# CrowPanel_ESP32_Display-4_3-inch-V2_1-20.net
KiCad netlist of a schematic drawn in EAGLE
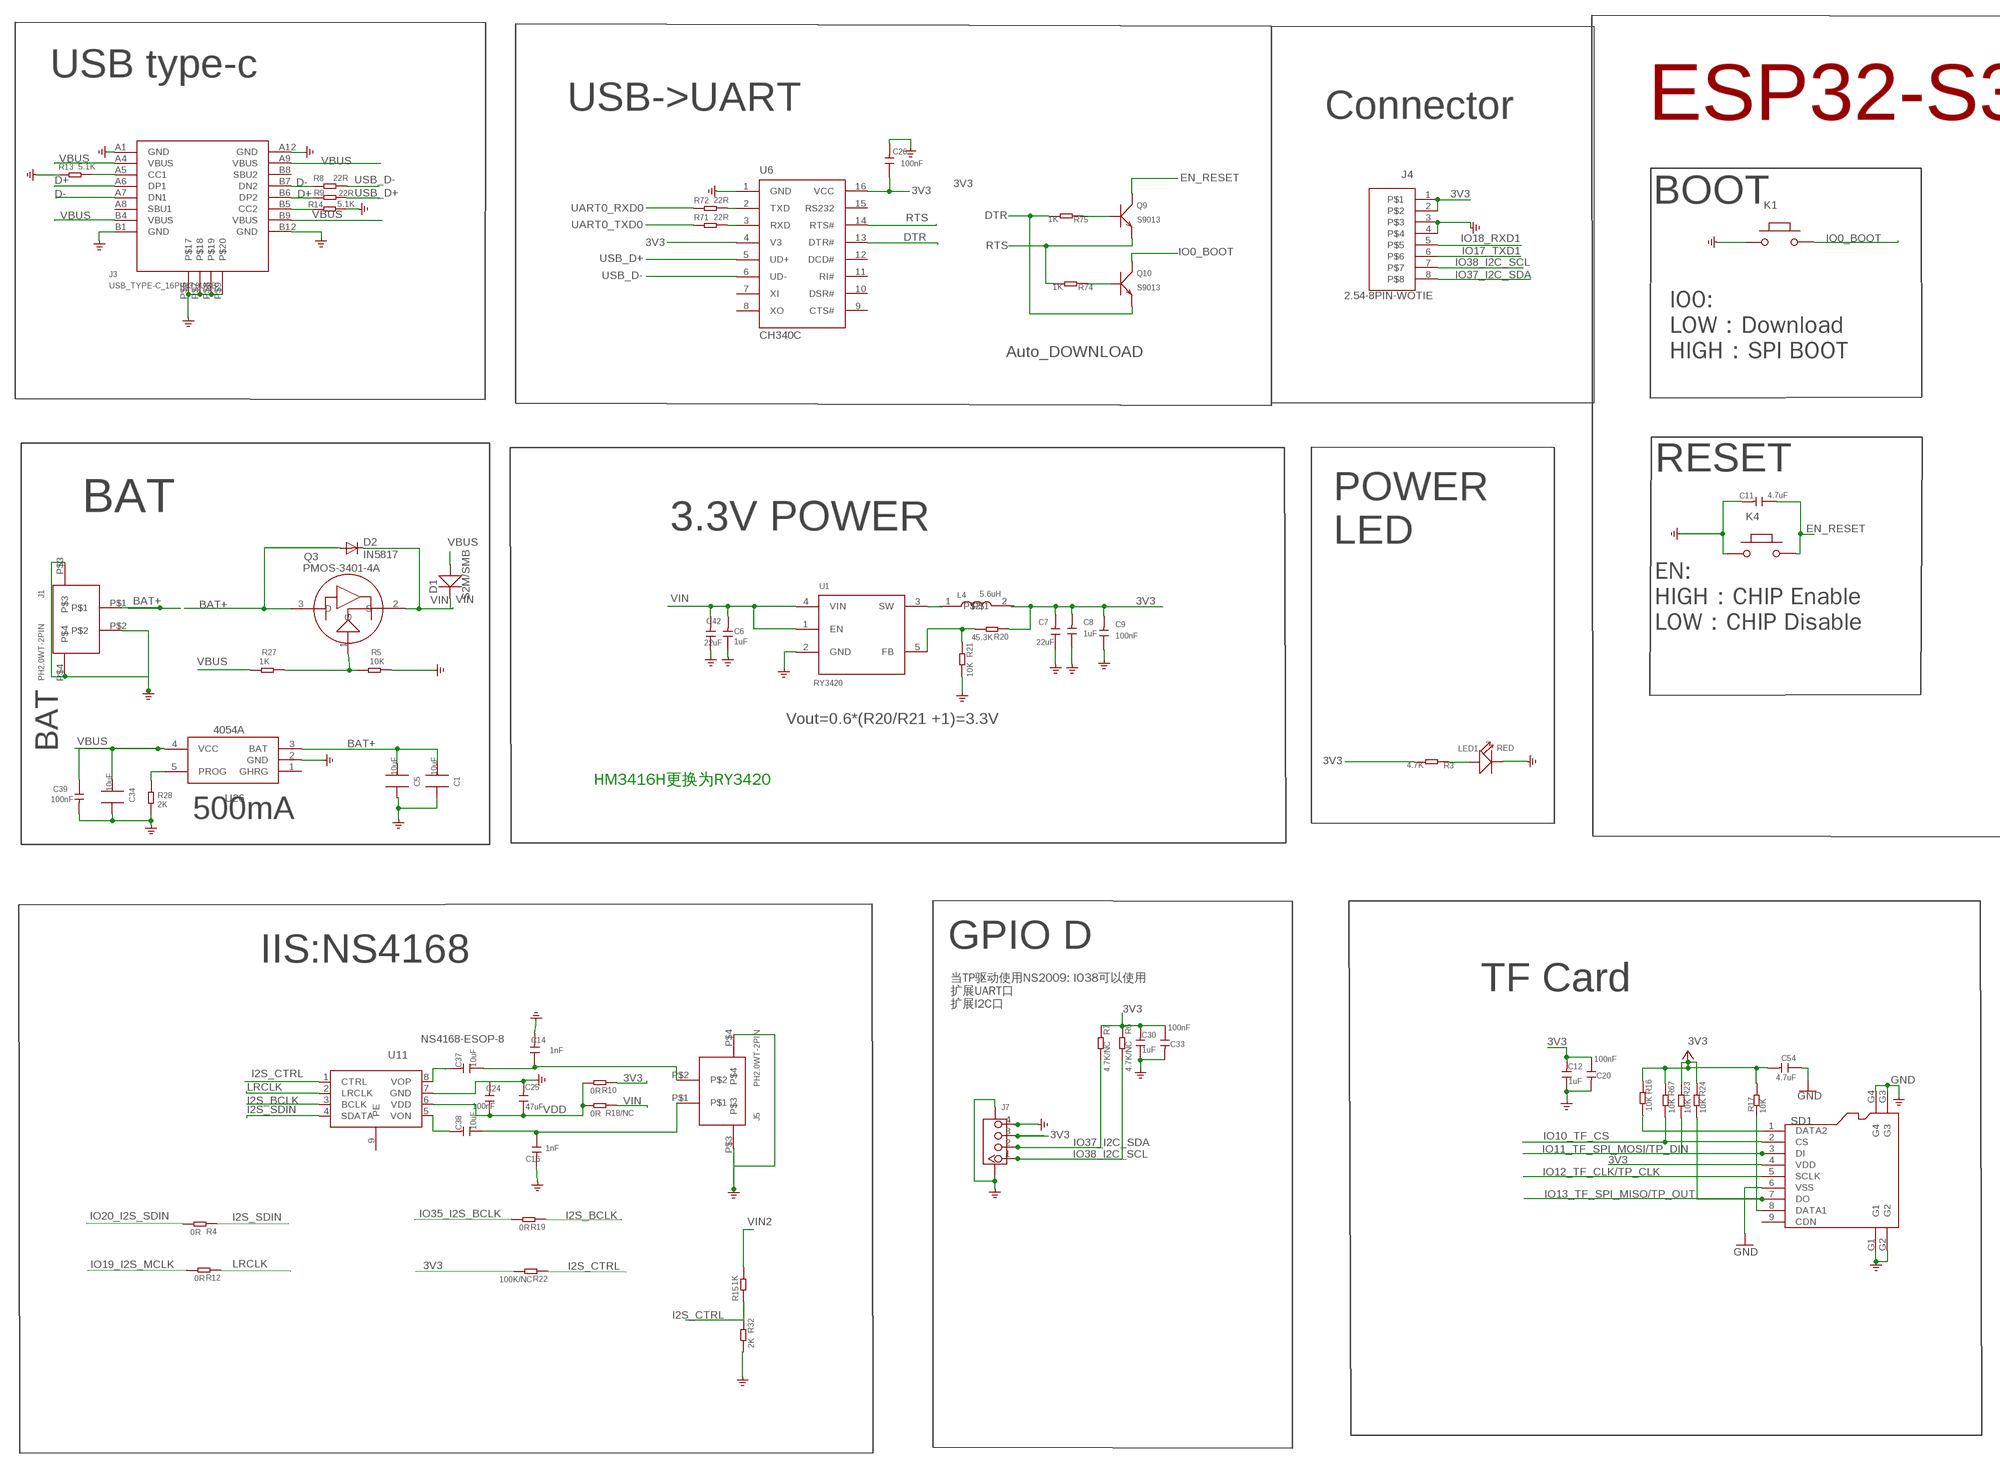
[diagram p0: schematic, sheet 1, part 1 of 2]
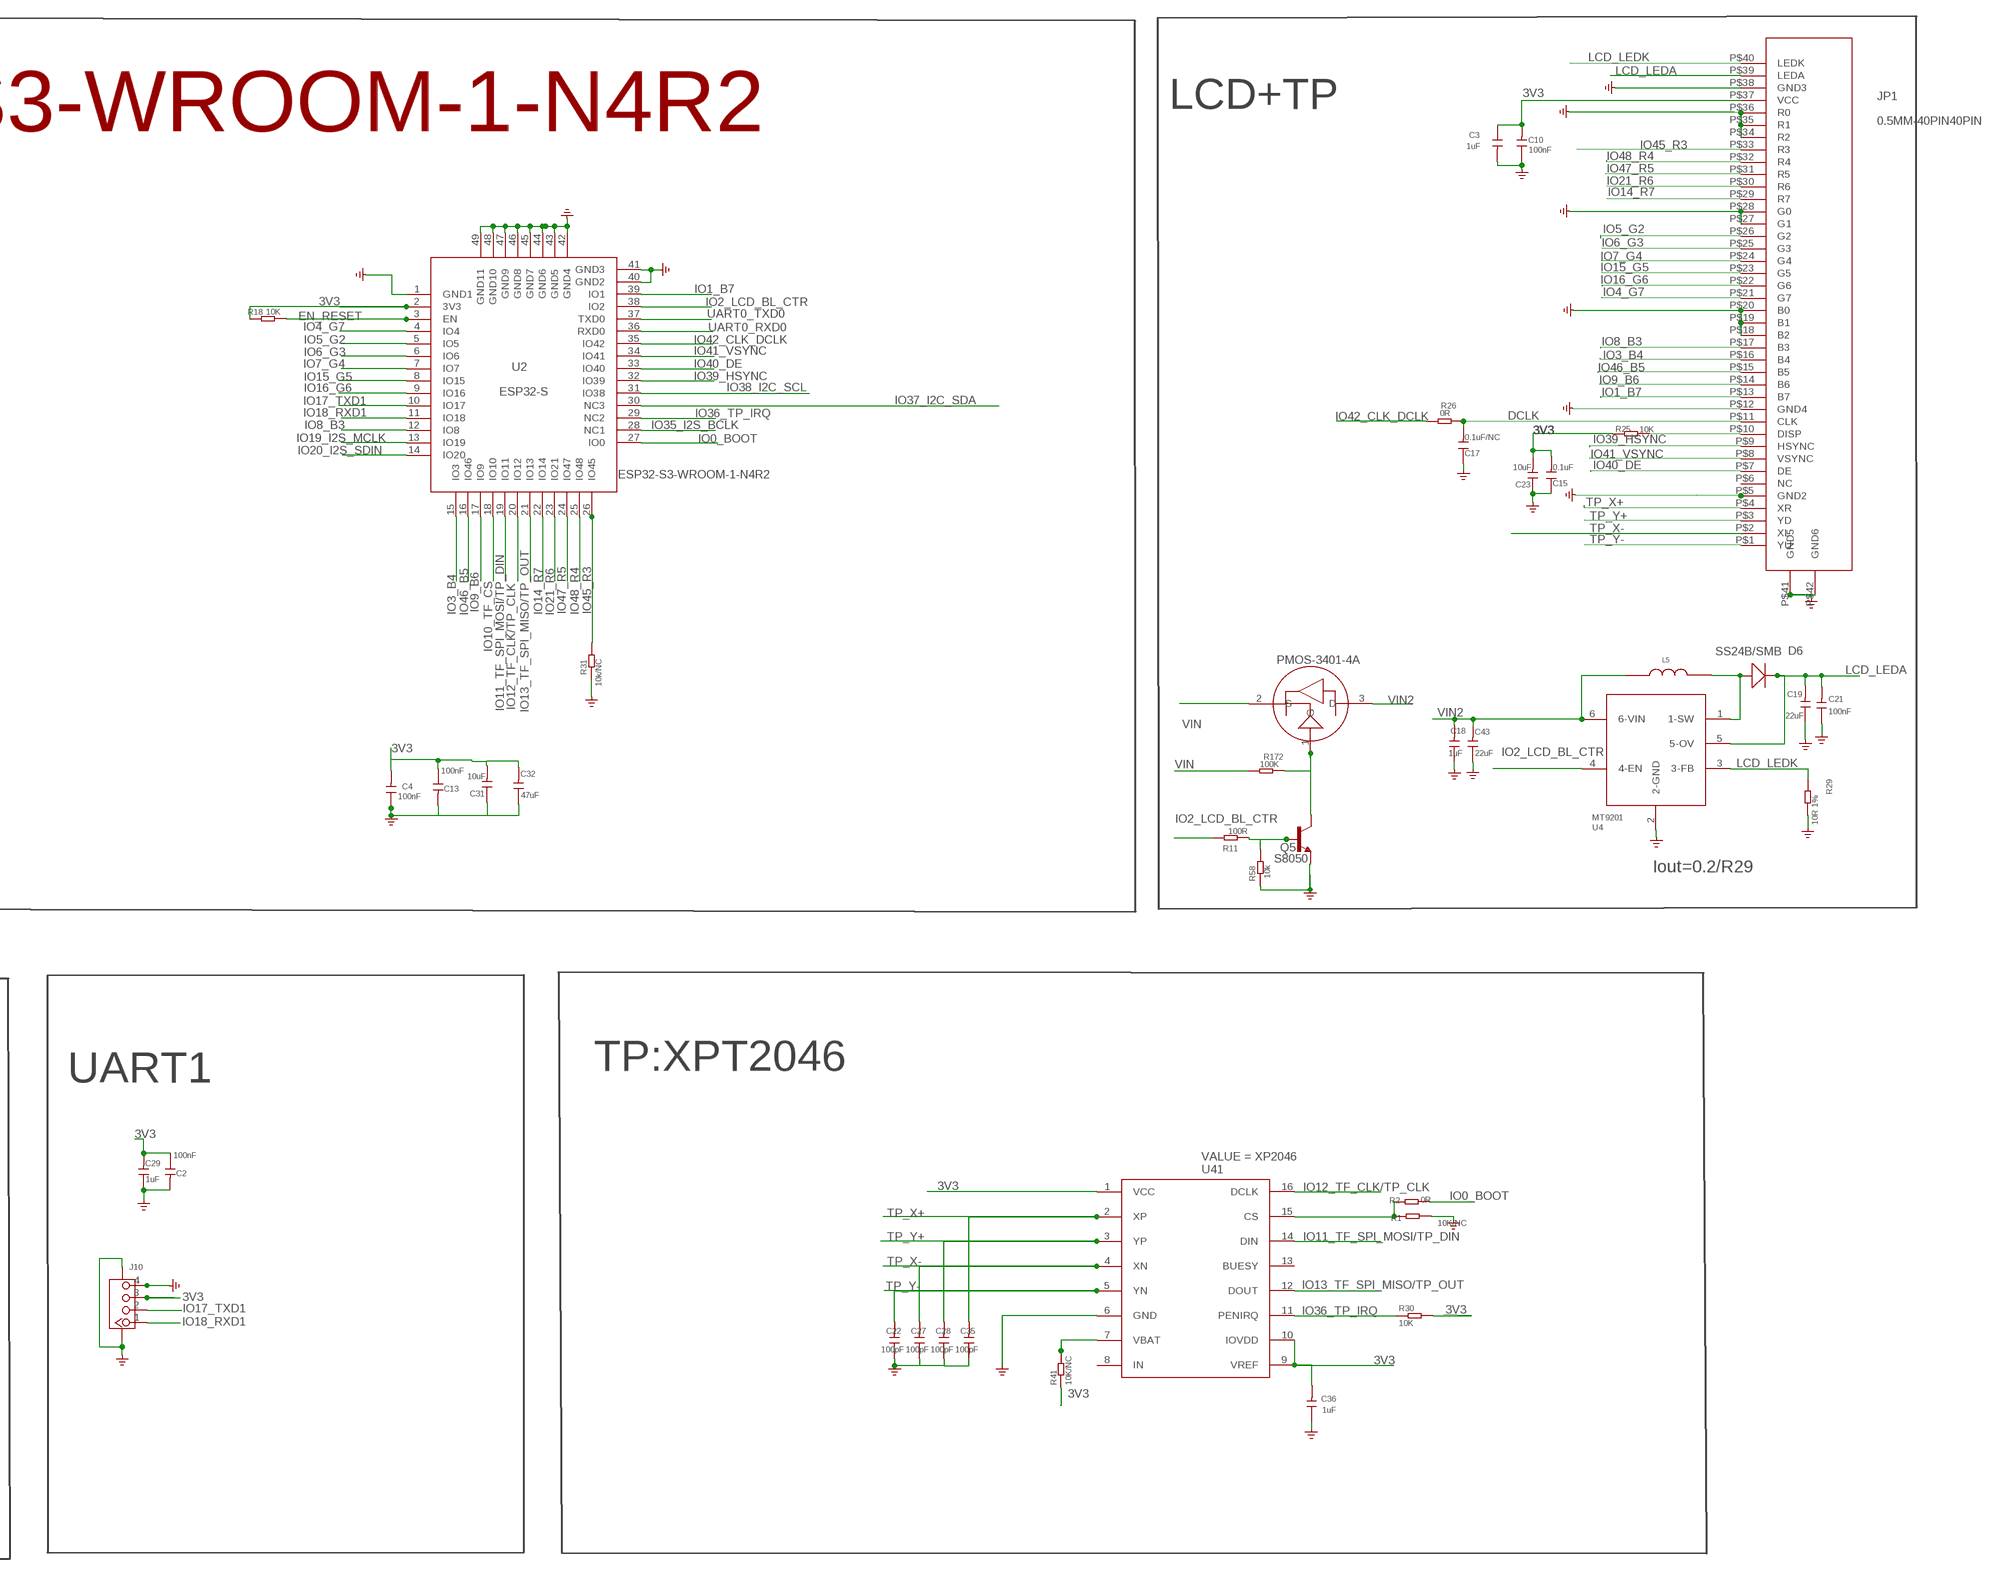
[diagram p1: schematic, sheet 1, part 2 of 2]

(export (version "E")
  (design (tool "Eeschema 10.0.6"))
  (components
    (comp (ref "C1")
      (value "10uF")
      (footprint "eagle-import:0805_S")
      (libsource (lib "eagle-import") (part "C0805_S"))
    )
    (comp (ref "C2")
      (value "100nF")
      (footprint "eagle-import:C0603")
      (libsource (lib "eagle-import") (part "C-0603"))
    )
    (comp (ref "C3")
      (value "1uF")
      (footprint "eagle-import:C0603")
      (libsource (lib "eagle-import") (part "C-0603"))
    )
    (comp (ref "C4")
      (value "100nF")
      (footprint "eagle-import:C0603")
      (libsource (lib "eagle-import") (part "C-0603"))
    )
    (comp (ref "C5")
      (value "10uF")
      (footprint "eagle-import:0805_S")
      (libsource (lib "eagle-import") (part "C0805_S"))
    )
    (comp (ref "C6")
      (value "1uF")
      (footprint "eagle-import:0603")
      (libsource (lib "eagle-import") (part "C0603"))
    )
    (comp (ref "C7")
      (value "22uF")
      (footprint "eagle-import:0805")
      (libsource (lib "eagle-import") (part "C0805"))
    )
    (comp (ref "C8")
      (value "1uF")
      (footprint "eagle-import:0603")
      (libsource (lib "eagle-import") (part "C0603"))
    )
    (comp (ref "C9")
      (value "100nF")
      (footprint "eagle-import:0603")
      (libsource (lib "eagle-import") (part "C0603"))
    )
    (comp (ref "C10")
      (value "100nF")
      (footprint "eagle-import:C0603")
      (libsource (lib "eagle-import") (part "C-0603"))
    )
    (comp (ref "C11")
      (value "4.7uF")
      (footprint "eagle-import:0603")
      (libsource (lib "eagle-import") (part "C0603"))
    )
    (comp (ref "C12")
      (value "1uF")
      (footprint "eagle-import:DISCRETE_C0603")
      (libsource (lib "eagle-import") (part "A_xbj_DISCRETE_C-0603"))
    )
    (comp (ref "C13")
      (value "100nF")
      (footprint "eagle-import:C0603")
      (libsource (lib "eagle-import") (part "C-0603"))
    )
    (comp (ref "C14")
      (value "1nF")
      (footprint "eagle-import:C0603")
      (libsource (lib "eagle-import") (part "C-0603"))
    )
    (comp (ref "C15")
      (value "0.1uF")
      (footprint "eagle-import:DISCRETE_C0603")
      (libsource (lib "eagle-import") (part "DISCRETE_C-0603"))
    )
    (comp (ref "C16")
      (value "1nF")
      (footprint "eagle-import:C0603")
      (libsource (lib "eagle-import") (part "C-0603"))
    )
    (comp (ref "C17")
      (value "0.1uF/NC")
      (footprint "eagle-import:DISCRETE_C0603")
      (libsource (lib "eagle-import") (part "DISCRETE_C-0603"))
    )
    (comp (ref "C18")
      (value "1uF")
      (footprint "eagle-import:0603")
      (libsource (lib "eagle-import") (part "C0603"))
    )
    (comp (ref "C19")
      (value "22uF")
      (footprint "eagle-import:0805")
      (libsource (lib "eagle-import") (part "C0805"))
    )
    (comp (ref "C20")
      (value "100nF")
      (footprint "eagle-import:C0603")
      (libsource (lib "eagle-import") (part "C-0603"))
    )
    (comp (ref "C21")
      (value "100nF")
      (footprint "eagle-import:0603")
      (libsource (lib "eagle-import") (part "C0603"))
    )
    (comp (ref "C22")
      (value "100pF")
      (footprint "eagle-import:0603")
      (libsource (lib "eagle-import") (part "C0603"))
    )
    (comp (ref "C23")
      (value "10uF")
      (footprint "eagle-import:DISCRETE_C0603")
      (libsource (lib "eagle-import") (part "DISCRETE_C-0603"))
    )
    (comp (ref "C24")
      (value "100nF")
      (footprint "eagle-import:C0603")
      (libsource (lib "eagle-import") (part "C-0603"))
    )
    (comp (ref "C25")
      (value "47uF")
      (footprint "eagle-import:0805")
      (libsource (lib "eagle-import") (part "C0805"))
    )
    (comp (ref "C26")
      (value "100nF")
      (footprint "eagle-import:0603")
      (libsource (lib "eagle-import") (part "C0603"))
    )
    (comp (ref "C27")
      (value "100pF")
      (footprint "eagle-import:0603")
      (libsource (lib "eagle-import") (part "C0603"))
    )
    (comp (ref "C28")
      (value "100pF")
      (footprint "eagle-import:0603")
      (libsource (lib "eagle-import") (part "C0603"))
    )
    (comp (ref "C29")
      (value "1uF")
      (footprint "eagle-import:DISCRETE_C0603")
      (libsource (lib "eagle-import") (part "A_xbj_DISCRETE_C-0603"))
    )
    (comp (ref "C30")
      (value "1uF")
      (footprint "eagle-import:DISCRETE_C0603")
      (libsource (lib "eagle-import") (part "A_xbj_DISCRETE_C-0603"))
    )
    (comp (ref "C31")
      (value "10uF")
      (footprint "eagle-import:DISCRETE_C0603")
      (libsource (lib "eagle-import") (part "DISCRETE_C-0603"))
    )
    (comp (ref "C32")
      (value "47uF")
      (footprint "eagle-import:0805")
      (libsource (lib "eagle-import") (part "C0805"))
    )
    (comp (ref "C33")
      (value "100nF")
      (footprint "eagle-import:C0603")
      (libsource (lib "eagle-import") (part "C-0603"))
    )
    (comp (ref "C34")
      (value "10uF")
      (footprint "eagle-import:0805_S")
      (libsource (lib "eagle-import") (part "C0805_S"))
    )
    (comp (ref "C35")
      (value "100pF")
      (footprint "eagle-import:0603")
      (libsource (lib "eagle-import") (part "C0603"))
    )
    (comp (ref "C36")
      (value "1uF")
      (footprint "eagle-import:DISCRETE_C0603")
      (libsource (lib "eagle-import") (part "A_xbj_DISCRETE_C-0603"))
    )
    (comp (ref "C37")
      (value "10uF")
      (footprint "eagle-import:DISCRETE_C0603")
      (libsource (lib "eagle-import") (part "A_xbj_DISCRETE_C-0603"))
    )
    (comp (ref "C38")
      (value "10uF")
      (footprint "eagle-import:DISCRETE_C0603")
      (libsource (lib "eagle-import") (part "A_xbj_DISCRETE_C-0603"))
    )
    (comp (ref "C39")
      (value "100nF")
      (footprint "eagle-import:C0603")
      (libsource (lib "eagle-import") (part "C-0603"))
    )
    (comp (ref "C42")
      (value "22uF")
      (footprint "eagle-import:0805")
      (libsource (lib "eagle-import") (part "C0805"))
    )
    (comp (ref "C43")
      (value "22uF")
      (footprint "eagle-import:0805")
      (libsource (lib "eagle-import") (part "C0805"))
    )
    (comp (ref "C54")
      (value "4.7uF")
      (footprint "eagle-import:DISCRETE_C0603")
      (libsource (lib "eagle-import") (part "DISCRETE_C-0603"))
    )
    (comp (ref "D1")
      (value "S2M/SMB")
      (footprint "eagle-import:214AB")
      (libsource (lib "eagle-import") (part "214ABDO-214AB"))
    )
    (comp (ref "D2")
      (value "IN5817")
      (footprint "eagle-import:DO-214AC")
      (libsource (lib "eagle-import") (part "DIODE-DO-214AC"))
    )
    (comp (ref "D6")
      (value "SS24B/SMB")
      (footprint "eagle-import:214AB")
      (libsource (lib "eagle-import") (part "214ABDO-214AB"))
    )
    (comp (ref "J1")
      (value "PH2.0WT-2PIN")
      (footprint "eagle-import:PH2.0WT-2PIN")
      (libsource (lib "eagle-import") (part "PH2.0WT-2PIN"))
    )
    (comp (ref "J3")
      (value "USB_TYPE-C_16PIN3.0USB")
      (footprint "eagle-import:KEVIN_3.0TYPEC-SMD")
      (libsource (lib "eagle-import") (part "USB_TYPE-C_16PIN3.0USB"))
    )
    (comp (ref "J4")
      (value "2.54-8PIN-WOTIE")
      (footprint "eagle-import:2.54-8P-WOTIE")
      (libsource (lib "eagle-import") (part "2.54-8PIN-WOTIE"))
    )
    (comp (ref "J5")
      (value "PH2.0WT-2PIN")
      (footprint "eagle-import:PH2.0WT-2PIN")
      (libsource (lib "eagle-import") (part "PH2.0WT-2PIN"))
    )
    (comp (ref "J7")
      (value "CONNECTOR_TWIG-4P-2.0-SMD-FEMALE-REINFORCE90D")
      (footprint "eagle-import:CONNECTOR_4P-SMD-2.0-90D")
      (libsource (lib "eagle-import") (part "CONNECTOR_TWIG-4P-2.0-SMD-FEMALE-REINFORCE90D"))
    )
    (comp (ref "J10")
      (value "CONNECTOR_TWIG-4P-2.0-SMD-FEMALE-REINFORCE90D")
      (footprint "eagle-import:CONNECTOR_4P-SMD-2.0-90D")
      (libsource (lib "eagle-import") (part "CONNECTOR_TWIG-4P-2.0-SMD-FEMALE-REINFORCE90D"))
    )
    (comp (ref "JP1")
      (value "0.5MM-40PIN40PIN")
      (footprint "eagle-import:0.5MM_40P")
      (libsource (lib "eagle-import") (part "0.5MM-40PIN40PIN"))
    )
    (comp (ref "K1")
      (value "BUTTON")
      (footprint "eagle-import:157SW")
      (libsource (lib "eagle-import") (part "PB157"))
    )
    (comp (ref "K4")
      (value "BUTTON")
      (footprint "eagle-import:157SW")
      (libsource (lib "eagle-import") (part "PB157"))
    )
    (comp (ref "L4")
      (value "5.6uH")
      (footprint "eagle-import:CD54_CD54")
      (libsource (lib "eagle-import") (part "L-0530"))
    )
    (comp (ref "L5")
      (value "CD32_6.8uH")
      (footprint "eagle-import:CD32")
      (libsource (lib "eagle-import") (part "CD32_950MA"))
    )
    (comp (ref "LED1")
      (value "RED")
      (footprint "eagle-import:DISCRETE_LED-0603")
      (libsource (lib "eagle-import") (part "DISCRETE_LED0603"))
    )
    (comp (ref "Q3")
      (value "PMOS-3401-4A")
      (footprint "eagle-import:SOT-23")
      (libsource (lib "eagle-import") (part "P-MOS-SOT23"))
    )
    (comp (ref "Q5")
      (value "S8050")
      (footprint "eagle-import:SPARKFUN_SOT23")
      (libsource (lib "eagle-import") (part "SPARKFUN_TRANSISTOR_NPNSOT23"))
    )
    (comp (ref "Q9")
      (value "S9013")
      (footprint "eagle-import:SOT23@1")
      (libsource (lib "eagle-import") (part "TRANSISTOR-NPN-SOT23"))
    )
    (comp (ref "Q10")
      (value "S9013")
      (footprint "eagle-import:SOT23@1")
      (libsource (lib "eagle-import") (part "TRANSISTOR-NPN-SOT23"))
    )
    (comp (ref "Q30")
      (value "PMOS-3401-4A")
      (footprint "eagle-import:SOT-23")
      (libsource (lib "eagle-import") (part "P-MOS-SOT23"))
    )
    (comp (ref "R1")
      (value "10K/NC")
      (footprint "eagle-import:R0603")
      (libsource (lib "eagle-import") (part "R0603"))
    )
    (comp (ref "R2")
      (value "0R")
      (footprint "eagle-import:DISCRETE_R0603")
      (libsource (lib "eagle-import") (part "Crowtail-_LED-V2.0-20190615-01_DISCRETE_R-0603"))
    )
    (comp (ref "R3")
      (value "4.7K")
      (footprint "eagle-import:DISCRETE_R0603")
      (libsource (lib "eagle-import") (part "Crowtail-_LED-V2.0-20190615-01_DISCRETE_R-0603"))
    )
    (comp (ref "R4")
      (value "0R")
      (footprint "eagle-import:DISCRETE_R0603")
      (libsource (lib "eagle-import") (part "Crowtail-_LED-V2.0-20190615-01_DISCRETE_R-0603"))
    )
    (comp (ref "R5")
      (value "10K")
      (footprint "eagle-import:DISCRETE_R0603")
      (libsource (lib "eagle-import") (part "DISCRETE_R-0603"))
    )
    (comp (ref "R6")
      (value "4.7K/NC")
      (footprint "eagle-import:DISCRETE_R0603")
      (libsource (lib "eagle-import") (part "Crowtail-_LED-V2.0-20190615-01_DISCRETE_R-0603"))
    )
    (comp (ref "R7")
      (value "4.7K/NC")
      (footprint "eagle-import:DISCRETE_R0603")
      (libsource (lib "eagle-import") (part "Crowtail-_LED-V2.0-20190615-01_DISCRETE_R-0603"))
    )
    (comp (ref "R8")
      (value "22R")
      (footprint "eagle-import:DISCRETE_R0603")
      (libsource (lib "eagle-import") (part "Crowtail-_LED-V2.0-20190615-01_DISCRETE_R-0603"))
    )
    (comp (ref "R9")
      (value "22R")
      (footprint "eagle-import:DISCRETE_R0603")
      (libsource (lib "eagle-import") (part "Crowtail-_LED-V2.0-20190615-01_DISCRETE_R-0603"))
    )
    (comp (ref "R10")
      (value "0R")
      (footprint "eagle-import:DISCRETE_R0603")
      (libsource (lib "eagle-import") (part "Crowtail-_LED-V2.0-20190615-01_DISCRETE_R-0603"))
    )
    (comp (ref "R11")
      (value "100R")
      (footprint "eagle-import:R0603")
      (libsource (lib "eagle-import") (part "R0603"))
    )
    (comp (ref "R12")
      (value "0R")
      (footprint "eagle-import:DISCRETE_R0603")
      (libsource (lib "eagle-import") (part "Crowtail-_LED-V2.0-20190615-01_DISCRETE_R-0603"))
    )
    (comp (ref "R13")
      (value "5.1K")
      (footprint "eagle-import:DISCRETE_R0603")
      (libsource (lib "eagle-import") (part "Crowtail-_LED-V2.0-20190615-01_DISCRETE_R-0603"))
    )
    (comp (ref "R14")
      (value "5.1K")
      (footprint "eagle-import:DISCRETE_R0603")
      (libsource (lib "eagle-import") (part "Crowtail-_LED-V2.0-20190615-01_DISCRETE_R-0603"))
    )
    (comp (ref "R15")
      (value "1K")
      (footprint "eagle-import:DISCRETE_R0603")
      (libsource (lib "eagle-import") (part "Crowtail-_LED-V2.0-20190615-01_DISCRETE_R-0603"))
    )
    (comp (ref "R16")
      (value "10K")
      (footprint "eagle-import:DISCRETE_R0603")
      (libsource (lib "eagle-import") (part "Crowtail-_LED-V2.0-20190615-01_DISCRETE_R-0603"))
    )
    (comp (ref "R17")
      (value "10K")
      (footprint "eagle-import:DISCRETE_R0603")
      (libsource (lib "eagle-import") (part "Crowtail-_LED-V2.0-20190615-01_DISCRETE_R-0603"))
    )
    (comp (ref "R18")
      (value "10K")
      (footprint "eagle-import:DISCRETE_R0603")
      (libsource (lib "eagle-import") (part "Crowtail-_LED-V2.0-20190615-01_DISCRETE_R-0603"))
    )
    (comp (ref "R18/NC")
      (value "0R")
      (footprint "eagle-import:DISCRETE_R0603")
      (libsource (lib "eagle-import") (part "Crowtail-_LED-V2.0-20190615-01_DISCRETE_R-0603"))
    )
    (comp (ref "R19")
      (value "0R")
      (footprint "eagle-import:DISCRETE_R0603")
      (libsource (lib "eagle-import") (part "Crowtail-_LED-V2.0-20190615-01_DISCRETE_R-0603"))
    )
    (comp (ref "R20")
      (value "45.3K")
      (footprint "eagle-import:DISCRETE_R0603")
      (libsource (lib "eagle-import") (part "Crowtail-_LED-V2.0-20190615-01_DISCRETE_R-0603"))
    )
    (comp (ref "R21")
      (value "10K")
      (footprint "eagle-import:DISCRETE_R0603")
      (libsource (lib "eagle-import") (part "Crowtail-_LED-V2.0-20190615-01_DISCRETE_R-0603"))
    )
    (comp (ref "R22")
      (value "100K/NC")
      (footprint "eagle-import:DISCRETE_R0603")
      (libsource (lib "eagle-import") (part "Crowtail-_LED-V2.0-20190615-01_DISCRETE_R-0603"))
    )
    (comp (ref "R23")
      (value "10K")
      (footprint "eagle-import:DISCRETE_R0603")
      (libsource (lib "eagle-import") (part "Crowtail-_LED-V2.0-20190615-01_DISCRETE_R-0603"))
    )
    (comp (ref "R24")
      (value "10K")
      (footprint "eagle-import:DISCRETE_R0603")
      (libsource (lib "eagle-import") (part "Crowtail-_LED-V2.0-20190615-01_DISCRETE_R-0603"))
    )
    (comp (ref "R25")
      (value "10K")
      (footprint "eagle-import:DISCRETE_R0603")
      (libsource (lib "eagle-import") (part "Crowtail-_LED-V2.0-20190615-01_DISCRETE_R-0603"))
    )
    (comp (ref "R26")
      (value "0R")
      (footprint "eagle-import:R0603")
      (libsource (lib "eagle-import") (part "R-0603"))
    )
    (comp (ref "R27")
      (value "1K")
      (footprint "eagle-import:DISCRETE_R0603")
      (libsource (lib "eagle-import") (part "DISCRETE_R-0603"))
    )
    (comp (ref "R28")
      (value "2K")
      (footprint "eagle-import:DISCRETE_R0603")
      (libsource (lib "eagle-import") (part "DISCRETE_R-0603"))
    )
    (comp (ref "R29")
      (value "10R 1%")
      (footprint "eagle-import:DISCRETE_R0603")
      (libsource (lib "eagle-import") (part "Crowtail-_LED-V2.0-20190615-01_DISCRETE_R-0603"))
    )
    (comp (ref "R30")
      (value "10K")
      (footprint "eagle-import:DISCRETE_R0603")
      (libsource (lib "eagle-import") (part "DISCRETE_R-0603"))
    )
    (comp (ref "R31")
      (value "10k/NC")
      (footprint "eagle-import:R0603")
      (libsource (lib "eagle-import") (part "R0603"))
    )
    (comp (ref "R32")
      (value "2K")
      (footprint "eagle-import:DISCRETE_R0603")
      (libsource (lib "eagle-import") (part "Crowtail-_LED-V2.0-20190615-01_DISCRETE_R-0603"))
    )
    (comp (ref "R41")
      (value "10K/NC")
      (footprint "eagle-import:DISCRETE_R0603")
      (libsource (lib "eagle-import") (part "DISCRETE_R-0603"))
    )
    (comp (ref "R58")
      (value "10k")
      (footprint "eagle-import:R0603")
      (libsource (lib "eagle-import") (part "R0603"))
    )
    (comp (ref "R67")
      (value "10K")
      (footprint "eagle-import:DISCRETE_R0603")
      (libsource (lib "eagle-import") (part "Crowtail-_LED-V2.0-20190615-01_DISCRETE_R-0603"))
    )
    (comp (ref "R71")
      (value "22R")
      (footprint "eagle-import:DISCRETE_R0603")
      (libsource (lib "eagle-import") (part "Crowtail-_LED-V2.0-20190615-01_DISCRETE_R-0603"))
    )
    (comp (ref "R72")
      (value "22R")
      (footprint "eagle-import:DISCRETE_R0603")
      (libsource (lib "eagle-import") (part "Crowtail-_LED-V2.0-20190615-01_DISCRETE_R-0603"))
    )
    (comp (ref "R74")
      (value "1K")
      (footprint "eagle-import:DISCRETE_R0603")
      (libsource (lib "eagle-import") (part "Crowtail-_LED-V2.0-20190615-01_DISCRETE_R-0603"))
    )
    (comp (ref "R75")
      (value "1K")
      (footprint "eagle-import:DISCRETE_R0603")
      (libsource (lib "eagle-import") (part "Crowtail-_LED-V2.0-20190615-01_DISCRETE_R-0603"))
    )
    (comp (ref "R172")
      (value "100K")
      (footprint "eagle-import:R0603")
      (libsource (lib "eagle-import") (part "R-0603"))
    )
    (comp (ref "SD1")
      (value "HOLDER-MICROSD-9P")
      (footprint "eagle-import:9P-SMD-W_-RING")
      (libsource (lib "eagle-import") (part "HOLDER-MICROSD-9P"))
    )
    (comp (ref "U1")
      (value "RY3420")
      (footprint "eagle-import:A_XBJ_SOT23-5")
      (libsource (lib "eagle-import") (part "A_XBJ_HM3420B"))
    )
    (comp (ref "U2")
      (value "ESP32-S")
      (footprint "eagle-import:ESP32-S3")
      (fields (field (name "U2") "ESP32-S3-WROOM-1-N4R2"))
      (libsource (lib "eagle-import") (part "ESP32-S"))
    )
    (comp (ref "U4")
      (value "MT9201")
      (footprint "eagle-import:SOT23-6")
      (libsource (lib "eagle-import") (part "MT9201"))
    )
    (comp (ref "U6")
      (value "CH340C")
      (footprint "eagle-import:SOP-16")
      (libsource (lib "eagle-import") (part "CH340G"))
    )
    (comp (ref "U11")
      (value "NS4168-ESOP-8")
      (footprint "eagle-import:NS4168-ESOP-8")
      (libsource (lib "eagle-import") (part "NS4168-ESOP-8"))
    )
    (comp (ref "U26")
      (value "4054A")
      (footprint "eagle-import:SOP23-5")
      (libsource (lib "eagle-import") (part "4054A"))
    )
    (comp (ref "U41")
      (value "XP2046")
      (footprint "eagle-import:XP2046-SSOP16")
      (libsource (lib "eagle-import") (part "XP2046"))
    )
  )
  (nets
    (net (code "1") (name "+3V3") (class "Default")
      (node (ref "C10") (pin "2") (pinfunction "2_2") (pintype "passive"))
      (node (ref "C12") (pin "2") (pinfunction "2_2") (pintype "passive"))
      (node (ref "C13") (pin "1") (pinfunction "1_1") (pintype "passive"))
      (node (ref "C15") (pin "2") (pinfunction "2_2") (pintype "passive"))
      (node (ref "C2") (pin "1") (pinfunction "1_1") (pintype "passive"))
      (node (ref "C20") (pin "1") (pinfunction "1_1") (pintype "passive"))
      (node (ref "C23") (pin "2") (pinfunction "2_2") (pintype "passive"))
      (node (ref "C26") (pin "1") (pinfunction "1_1") (pintype "passive"))
      (node (ref "C29") (pin "2") (pinfunction "2_2") (pintype "passive"))
      (node (ref "C3") (pin "1") (pinfunction "1_1") (pintype "passive"))
      (node (ref "C30") (pin "2") (pinfunction "2_2") (pintype "passive"))
      (node (ref "C31") (pin "2") (pinfunction "2_2") (pintype "passive"))
      (node (ref "C32") (pin "2") (pinfunction "2_2") (pintype "passive"))
      (node (ref "C33") (pin "1") (pinfunction "1_1") (pintype "passive"))
      (node (ref "C36") (pin "2") (pinfunction "2_2") (pintype "passive"))
      (node (ref "C4") (pin "2") (pinfunction "2_2") (pintype "passive"))
      (node (ref "C54") (pin "2") (pinfunction "2_2") (pintype "passive"))
      (node (ref "C7") (pin "2") (pinfunction "2_2") (pintype "passive"))
      (node (ref "C8") (pin "2") (pinfunction "2_2") (pintype "passive"))
      (node (ref "C9") (pin "2") (pinfunction "2_2") (pintype "passive"))
      (node (ref "J10") (pin "3") (pinfunction "3_3") (pintype "bidirectional"))
      (node (ref "J4") (pin "1") (pinfunction "P$1_1") (pintype "bidirectional"))
      (node (ref "J4") (pin "2") (pinfunction "P$2_2") (pintype "bidirectional"))
      (node (ref "J7") (pin "3") (pinfunction "3_3") (pintype "bidirectional"))
      (node (ref "JP1") (pin "P$37") (pinfunction "VCC_P$37") (pintype "bidirectional"))
      (node (ref "L4") (pin "2") (pinfunction "P$2_2") (pintype "bidirectional"))
      (node (ref "R10") (pin "1") (pinfunction "1_1") (pintype "passive"))
      (node (ref "R16") (pin "1") (pinfunction "1_1") (pintype "passive"))
      (node (ref "R17") (pin "1") (pinfunction "1_1") (pintype "passive"))
      (node (ref "R18") (pin "1") (pinfunction "1_1") (pintype "passive"))
      (node (ref "R20") (pin "1") (pinfunction "1_1") (pintype "passive"))
      (node (ref "R22") (pin "2") (pinfunction "2_2") (pintype "passive"))
      (node (ref "R23") (pin "1") (pinfunction "1_1") (pintype "passive"))
      (node (ref "R24") (pin "1") (pinfunction "1_1") (pintype "passive"))
      (node (ref "R25") (pin "1") (pinfunction "1_1") (pintype "passive"))
      (node (ref "R3") (pin "2") (pinfunction "2_2") (pintype "passive"))
      (node (ref "R30") (pin "2") (pinfunction "2_2") (pintype "passive"))
      (node (ref "R41") (pin "1") (pinfunction "1_1") (pintype "passive"))
      (node (ref "R6") (pin "1") (pinfunction "1_1") (pintype "passive"))
      (node (ref "R67") (pin "1") (pinfunction "1_1") (pintype "passive"))
      (node (ref "R7") (pin "1") (pinfunction "1_1") (pintype "passive"))
      (node (ref "SD1") (pin "4") (pinfunction "VDD_4") (pintype "bidirectional"))
      (node (ref "U2") (pin "2") (pinfunction "3V3_2") (pintype "bidirectional"))
      (node (ref "U41") (pin "1") (pinfunction "VCC_1") (pintype "bidirectional"))
      (node (ref "U41") (pin "10") (pinfunction "IOVDD_10") (pintype "bidirectional"))
      (node (ref "U41") (pin "9") (pinfunction "VREF_9") (pintype "bidirectional"))
      (node (ref "U6") (pin "16") (pinfunction "VCC_16") (pintype "bidirectional"))
      (node (ref "U6") (pin "4") (pinfunction "V3_4") (pintype "bidirectional"))
    )
    (net (code "2") (name "/BAT+") (class "Default")
      (node (ref "C1") (pin "2") (pinfunction "2_2") (pintype "bidirectional"))
      (node (ref "C5") (pin "2") (pinfunction "2_2") (pintype "bidirectional"))
      (node (ref "D2") (pin "A") (pinfunction "A_A") (pintype "passive"))
      (node (ref "J1") (pin "P$1") (pinfunction "P$1_P$1") (pintype "bidirectional"))
      (node (ref "Q3") (pin "3") (pinfunction "D_3") (pintype "bidirectional"))
      (node (ref "U26") (pin "3") (pinfunction "BAT_3") (pintype "bidirectional"))
    )
    (net (code "3") (name "/D+") (class "Default")
      (node (ref "J3") (pin "A6") (pinfunction "DP1_A6") (pintype "bidirectional"))
      (node (ref "J3") (pin "B6") (pinfunction "DP2_B6") (pintype "bidirectional"))
      (node (ref "R9") (pin "1") (pinfunction "1_1") (pintype "passive"))
    )
    (net (code "4") (name "/D-") (class "Default")
      (node (ref "J3") (pin "A7") (pinfunction "DN1_A7") (pintype "bidirectional"))
      (node (ref "J3") (pin "B7") (pinfunction "DN2_B7") (pintype "bidirectional"))
      (node (ref "R8") (pin "1") (pinfunction "1_1") (pintype "passive"))
    )
    (net (code "5") (name "/DCLK") (class "Default")
      (node (ref "C17") (pin "2") (pinfunction "2_2") (pintype "passive"))
      (node (ref "JP1") (pin "P$11") (pinfunction "CLK_P$11") (pintype "bidirectional"))
      (node (ref "R26") (pin "2") (pinfunction "2_2") (pintype "passive"))
    )
    (net (code "6") (name "/DTR") (class "Default")
      (node (ref "Q10") (pin "2") (pinfunction "E_2") (pintype "passive"))
      (node (ref "R75") (pin "2") (pinfunction "2_2") (pintype "passive"))
      (node (ref "U6") (pin "13") (pinfunction "DTR#_13") (pintype "bidirectional"))
    )
    (net (code "7") (name "/EN_RESET") (class "Default")
      (node (ref "C11") (pin "1") (pinfunction "1_1") (pintype "passive"))
      (node (ref "K4") (pin "2") (pinfunction "2_2") (pintype "passive"))
      (node (ref "Q9") (pin "3") (pinfunction "C_3") (pintype "passive"))
      (node (ref "R18") (pin "2") (pinfunction "2_2") (pintype "passive"))
      (node (ref "U2") (pin "3") (pinfunction "EN_3") (pintype "bidirectional"))
    )
    (net (code "8") (name "/I2S_BCLK") (class "Default")
      (node (ref "R19") (pin "1") (pinfunction "1_1") (pintype "passive"))
      (node (ref "U11") (pin "3") (pinfunction "BCLK_3") (pintype "bidirectional"))
    )
    (net (code "9") (name "/I2S_CTRL") (class "Default")
      (node (ref "R15") (pin "1") (pinfunction "1_1") (pintype "passive"))
      (node (ref "R22") (pin "1") (pinfunction "1_1") (pintype "passive"))
      (node (ref "R32") (pin "1") (pinfunction "1_1") (pintype "passive"))
      (node (ref "U11") (pin "1") (pinfunction "CTRL_1") (pintype "bidirectional"))
    )
    (net (code "10") (name "/I2S_SDIN") (class "Default")
      (node (ref "R4") (pin "1") (pinfunction "1_1") (pintype "passive"))
      (node (ref "U11") (pin "4") (pinfunction "SDATA_4") (pintype "bidirectional"))
    )
    (net (code "11") (name "/IO0_BOOT") (class "Default")
      (node (ref "K1") (pin "2") (pinfunction "2_2") (pintype "passive"))
      (node (ref "Q10") (pin "3") (pinfunction "C_3") (pintype "passive"))
      (node (ref "R2") (pin "1") (pinfunction "1_1") (pintype "passive"))
      (node (ref "U2") (pin "27") (pinfunction "IO0_27") (pintype "bidirectional"))
    )
    (net (code "12") (name "/IO1_B7") (class "Default")
      (node (ref "JP1") (pin "P$13") (pinfunction "B7_P$13") (pintype "bidirectional"))
      (node (ref "U2") (pin "39") (pinfunction "IO1_39") (pintype "bidirectional"))
    )
    (net (code "13") (name "/IO2_LCD_BL_CTR") (class "Default")
      (node (ref "R11") (pin "2") (pinfunction "2_2") (pintype "passive"))
      (node (ref "U2") (pin "38") (pinfunction "IO2_38") (pintype "bidirectional"))
      (node (ref "U4") (pin "4") (pinfunction "4-EN_4") (pintype "bidirectional"))
    )
    (net (code "14") (name "/IO3_B4") (class "Default")
      (node (ref "JP1") (pin "P$16") (pinfunction "B4_P$16") (pintype "bidirectional"))
      (node (ref "U2") (pin "15") (pinfunction "IO3_15") (pintype "bidirectional"))
    )
    (net (code "15") (name "/IO4_G7") (class "Default")
      (node (ref "JP1") (pin "P$21") (pinfunction "G7_P$21") (pintype "bidirectional"))
      (node (ref "U2") (pin "4") (pinfunction "IO4_4") (pintype "bidirectional"))
    )
    (net (code "16") (name "/IO5_G2") (class "Default")
      (node (ref "JP1") (pin "P$26") (pinfunction "G2_P$26") (pintype "bidirectional"))
      (node (ref "U2") (pin "5") (pinfunction "IO5_5") (pintype "bidirectional"))
    )
    (net (code "17") (name "/IO6_G3") (class "Default")
      (node (ref "JP1") (pin "P$25") (pinfunction "G3_P$25") (pintype "bidirectional"))
      (node (ref "U2") (pin "6") (pinfunction "IO6_6") (pintype "bidirectional"))
    )
    (net (code "18") (name "/IO7_G4") (class "Default")
      (node (ref "JP1") (pin "P$24") (pinfunction "G4_P$24") (pintype "bidirectional"))
      (node (ref "U2") (pin "7") (pinfunction "IO7_7") (pintype "bidirectional"))
    )
    (net (code "19") (name "/IO8_B3") (class "Default")
      (node (ref "JP1") (pin "P$17") (pinfunction "B3_P$17") (pintype "bidirectional"))
      (node (ref "U2") (pin "12") (pinfunction "IO8_12") (pintype "bidirectional"))
    )
    (net (code "20") (name "/IO9_B6") (class "Default")
      (node (ref "JP1") (pin "P$14") (pinfunction "B6_P$14") (pintype "bidirectional"))
      (node (ref "U2") (pin "17") (pinfunction "IO9_17") (pintype "bidirectional"))
    )
    (net (code "21") (name "/IO10_TF_CS") (class "Default")
      (node (ref "R67") (pin "2") (pinfunction "2_2") (pintype "passive"))
      (node (ref "SD1") (pin "2") (pinfunction "CS_2") (pintype "bidirectional"))
      (node (ref "U2") (pin "18") (pinfunction "IO10_18") (pintype "bidirectional"))
    )
    (net (code "22") (name "/IO11_TF_SPI_MOSI{slash}TP_DIN") (class "Default")
      (node (ref "R23") (pin "2") (pinfunction "2_2") (pintype "passive"))
      (node (ref "SD1") (pin "3") (pinfunction "DI_3") (pintype "bidirectional"))
      (node (ref "U2") (pin "19") (pinfunction "IO11_19") (pintype "bidirectional"))
      (node (ref "U41") (pin "14") (pinfunction "DIN_14") (pintype "bidirectional"))
    )
    (net (code "23") (name "/IO12_TF_CLK{slash}TP_CLK") (class "Default")
      (node (ref "SD1") (pin "5") (pinfunction "SCLK_5") (pintype "bidirectional"))
      (node (ref "U2") (pin "20") (pinfunction "IO12_20") (pintype "bidirectional"))
      (node (ref "U41") (pin "16") (pinfunction "DCLK_16") (pintype "bidirectional"))
    )
    (net (code "24") (name "/IO13_TF_SPI_MISO{slash}TP_OUT") (class "Default")
      (node (ref "R24") (pin "2") (pinfunction "2_2") (pintype "passive"))
      (node (ref "SD1") (pin "7") (pinfunction "DO_7") (pintype "bidirectional"))
      (node (ref "U2") (pin "21") (pinfunction "IO13_21") (pintype "bidirectional"))
      (node (ref "U41") (pin "12") (pinfunction "DOUT_12") (pintype "bidirectional"))
    )
    (net (code "25") (name "/IO14_R7") (class "Default")
      (node (ref "JP1") (pin "P$29") (pinfunction "R7_P$29") (pintype "bidirectional"))
      (node (ref "U2") (pin "22") (pinfunction "IO14_22") (pintype "bidirectional"))
    )
    (net (code "26") (name "/IO15_G5") (class "Default")
      (node (ref "JP1") (pin "P$23") (pinfunction "G5_P$23") (pintype "bidirectional"))
      (node (ref "U2") (pin "8") (pinfunction "IO15_8") (pintype "bidirectional"))
    )
    (net (code "27") (name "/IO16_G6") (class "Default")
      (node (ref "JP1") (pin "P$22") (pinfunction "G6_P$22") (pintype "bidirectional"))
      (node (ref "U2") (pin "9") (pinfunction "IO16_9") (pintype "bidirectional"))
    )
    (net (code "28") (name "/IO17_TXD1") (class "Default")
      (node (ref "J10") (pin "2") (pinfunction "2_2") (pintype "bidirectional"))
      (node (ref "J4") (pin "6") (pinfunction "P$6_6") (pintype "bidirectional"))
      (node (ref "U2") (pin "10") (pinfunction "IO17_10") (pintype "bidirectional"))
    )
    (net (code "29") (name "/IO18_RXD1") (class "Default")
      (node (ref "J10") (pin "1") (pinfunction "1_1") (pintype "bidirectional"))
      (node (ref "J4") (pin "5") (pinfunction "P$5_5") (pintype "bidirectional"))
      (node (ref "U2") (pin "11") (pinfunction "IO18_11") (pintype "bidirectional"))
    )
    (net (code "30") (name "/IO19_I2S_MCLK") (class "Default")
      (node (ref "R12") (pin "2") (pinfunction "2_2") (pintype "passive"))
      (node (ref "U2") (pin "13") (pinfunction "IO19_13") (pintype "bidirectional"))
    )
    (net (code "31") (name "/IO20_I2S_SDIN") (class "Default")
      (node (ref "R4") (pin "2") (pinfunction "2_2") (pintype "passive"))
      (node (ref "U2") (pin "14") (pinfunction "IO20_14") (pintype "bidirectional"))
    )
    (net (code "32") (name "/IO21_R6") (class "Default")
      (node (ref "JP1") (pin "P$30") (pinfunction "R6_P$30") (pintype "bidirectional"))
      (node (ref "U2") (pin "23") (pinfunction "IO21_23") (pintype "bidirectional"))
    )
    (net (code "33") (name "/IO35_I2S_BCLK") (class "Default")
      (node (ref "R19") (pin "2") (pinfunction "2_2") (pintype "passive"))
      (node (ref "U2") (pin "28") (pinfunction "NC1_28") (pintype "bidirectional"))
    )
    (net (code "34") (name "/IO36_TP_IRQ") (class "Default")
      (node (ref "R30") (pin "1") (pinfunction "1_1") (pintype "passive"))
      (node (ref "U2") (pin "29") (pinfunction "NC2_29") (pintype "bidirectional"))
      (node (ref "U41") (pin "11") (pinfunction "PENIRQ_11") (pintype "bidirectional"))
    )
    (net (code "35") (name "/IO37_I2C_SDA") (class "Default")
      (node (ref "J4") (pin "8") (pinfunction "P$8_8") (pintype "bidirectional"))
      (node (ref "J7") (pin "2") (pinfunction "2_2") (pintype "bidirectional"))
      (node (ref "R7") (pin "2") (pinfunction "2_2") (pintype "passive"))
      (node (ref "U2") (pin "30") (pinfunction "NC3_30") (pintype "bidirectional"))
    )
    (net (code "36") (name "/IO38_I2C_SCL") (class "Default")
      (node (ref "J4") (pin "7") (pinfunction "P$7_7") (pintype "bidirectional"))
      (node (ref "J7") (pin "1") (pinfunction "1_1") (pintype "bidirectional"))
      (node (ref "R6") (pin "2") (pinfunction "2_2") (pintype "passive"))
      (node (ref "U2") (pin "31") (pinfunction "IO38_31") (pintype "bidirectional"))
    )
    (net (code "37") (name "/IO39_HSYNC") (class "Default")
      (node (ref "JP1") (pin "P$9") (pinfunction "HSYNC_P$9") (pintype "bidirectional"))
      (node (ref "U2") (pin "32") (pinfunction "IO39_32") (pintype "bidirectional"))
    )
    (net (code "38") (name "/IO40_DE") (class "Default")
      (node (ref "JP1") (pin "P$7") (pinfunction "DE_P$7") (pintype "bidirectional"))
      (node (ref "U2") (pin "33") (pinfunction "IO40_33") (pintype "bidirectional"))
    )
    (net (code "39") (name "/IO41_VSYNC") (class "Default")
      (node (ref "JP1") (pin "P$8") (pinfunction "VSYNC_P$8") (pintype "bidirectional"))
      (node (ref "U2") (pin "34") (pinfunction "IO41_34") (pintype "bidirectional"))
    )
    (net (code "40") (name "/IO42_CLK_DCLK") (class "Default")
      (node (ref "R26") (pin "1") (pinfunction "1_1") (pintype "passive"))
      (node (ref "U2") (pin "35") (pinfunction "IO42_35") (pintype "bidirectional"))
    )
    (net (code "41") (name "/IO45_R3") (class "Default")
      (node (ref "JP1") (pin "P$33") (pinfunction "R3_P$33") (pintype "bidirectional"))
      (node (ref "R31") (pin "2") (pinfunction "2_2") (pintype "passive"))
      (node (ref "U2") (pin "26") (pinfunction "IO45_26") (pintype "bidirectional"))
    )
    (net (code "42") (name "/IO46_B5") (class "Default")
      (node (ref "JP1") (pin "P$15") (pinfunction "B5_P$15") (pintype "bidirectional"))
      (node (ref "U2") (pin "16") (pinfunction "IO46_16") (pintype "bidirectional"))
    )
    (net (code "43") (name "/IO47_R5") (class "Default")
      (node (ref "JP1") (pin "P$31") (pinfunction "R5_P$31") (pintype "bidirectional"))
      (node (ref "U2") (pin "24") (pinfunction "IO47_24") (pintype "bidirectional"))
    )
    (net (code "44") (name "/IO48_R4") (class "Default")
      (node (ref "JP1") (pin "P$32") (pinfunction "R4_P$32") (pintype "bidirectional"))
      (node (ref "U2") (pin "25") (pinfunction "IO48_25") (pintype "bidirectional"))
    )
    (net (code "45") (name "/LCD_LEDA") (class "Default")
      (node (ref "C19") (pin "2") (pinfunction "2_2") (pintype "passive"))
      (node (ref "C21") (pin "2") (pinfunction "2_2") (pintype "passive"))
      (node (ref "D6") (pin "2") (pinfunction "-_2") (pintype "passive"))
      (node (ref "JP1") (pin "P$39") (pinfunction "LEDA_P$39") (pintype "bidirectional"))
      (node (ref "U4") (pin "5") (pinfunction "5-OV_5") (pintype "bidirectional"))
    )
    (net (code "46") (name "/LCD_LEDK") (class "Default")
      (node (ref "JP1") (pin "P$40") (pinfunction "LEDK_P$40") (pintype "bidirectional"))
      (node (ref "R29") (pin "1") (pinfunction "1_1") (pintype "passive"))
      (node (ref "U4") (pin "3") (pinfunction "3-FB_3") (pintype "bidirectional"))
    )
    (net (code "47") (name "/LRCLK") (class "Default")
      (node (ref "R12") (pin "1") (pinfunction "1_1") (pintype "passive"))
      (node (ref "U11") (pin "2") (pinfunction "LRCLK_2") (pintype "bidirectional"))
    )
    (net (code "48") (name "/RTS") (class "Default")
      (node (ref "Q9") (pin "2") (pinfunction "E_2") (pintype "passive"))
      (node (ref "R74") (pin "2") (pinfunction "2_2") (pintype "passive"))
      (node (ref "U6") (pin "14") (pinfunction "RTS#_14") (pintype "bidirectional"))
    )
    (net (code "49") (name "/TP_X+") (class "Default")
      (node (ref "C35") (pin "2") (pinfunction "2_2") (pintype "passive"))
      (node (ref "JP1") (pin "P$4") (pinfunction "XR_P$4") (pintype "bidirectional"))
      (node (ref "U41") (pin "2") (pinfunction "XP_2") (pintype "bidirectional"))
    )
    (net (code "50") (name "/TP_X-") (class "Default")
      (node (ref "C27") (pin "2") (pinfunction "2_2") (pintype "passive"))
      (node (ref "JP1") (pin "P$2") (pinfunction "XL_P$2") (pintype "bidirectional"))
      (node (ref "U41") (pin "4") (pinfunction "XN_4") (pintype "bidirectional"))
    )
    (net (code "51") (name "/TP_Y+") (class "Default")
      (node (ref "C28") (pin "2") (pinfunction "2_2") (pintype "passive"))
      (node (ref "JP1") (pin "P$3") (pinfunction "YD_P$3") (pintype "bidirectional"))
      (node (ref "U41") (pin "3") (pinfunction "YP_3") (pintype "bidirectional"))
    )
    (net (code "52") (name "/TP_Y-") (class "Default")
      (node (ref "C22") (pin "2") (pinfunction "2_2") (pintype "passive"))
      (node (ref "JP1") (pin "P$1") (pinfunction "YU_P$1") (pintype "bidirectional"))
      (node (ref "U41") (pin "5") (pinfunction "YN_5") (pintype "bidirectional"))
    )
    (net (code "53") (name "/UART0_RXD0") (class "Default")
      (node (ref "R72") (pin "1") (pinfunction "1_1") (pintype "passive"))
      (node (ref "U2") (pin "36") (pinfunction "RXD0_36") (pintype "bidirectional"))
    )
    (net (code "54") (name "/UART0_TXD0") (class "Default")
      (node (ref "R71") (pin "1") (pinfunction "1_1") (pintype "passive"))
      (node (ref "U2") (pin "37") (pinfunction "TXD0_37") (pintype "bidirectional"))
    )
    (net (code "55") (name "/USB_D+") (class "Default")
      (node (ref "R9") (pin "2") (pinfunction "2_2") (pintype "passive"))
      (node (ref "U6") (pin "5") (pinfunction "UD+_5") (pintype "bidirectional"))
    )
    (net (code "56") (name "/USB_D-") (class "Default")
      (node (ref "R8") (pin "2") (pinfunction "2_2") (pintype "passive"))
      (node (ref "U6") (pin "6") (pinfunction "UD-_6") (pintype "bidirectional"))
    )
    (net (code "57") (name "/VBUS") (class "Default")
      (node (ref "C34") (pin "2") (pinfunction "2_2") (pintype "bidirectional"))
      (node (ref "C39") (pin "1") (pinfunction "1_1") (pintype "passive"))
      (node (ref "D1") (pin "1") (pinfunction "+_1") (pintype "passive"))
      (node (ref "J3") (pin "A4") (pinfunction "VBUS_A4") (pintype "bidirectional"))
      (node (ref "J3") (pin "A9") (pinfunction "VBUS_A9") (pintype "bidirectional"))
      (node (ref "J3") (pin "B4") (pinfunction "VBUS_B4") (pintype "bidirectional"))
      (node (ref "J3") (pin "B9") (pinfunction "VBUS_B9") (pintype "bidirectional"))
      (node (ref "R27") (pin "2") (pinfunction "2_2") (pintype "passive"))
      (node (ref "U26") (pin "4") (pinfunction "VCC_4") (pintype "bidirectional"))
    )
    (net (code "58") (name "/VDD") (class "Default")
      (node (ref "C24") (pin "1") (pinfunction "1_1") (pintype "passive"))
      (node (ref "C25") (pin "1") (pinfunction "1_1") (pintype "passive"))
      (node (ref "R10") (pin "2") (pinfunction "2_2") (pintype "passive"))
      (node (ref "R18/NC") (pin "2") (pinfunction "2_2") (pintype "passive"))
      (node (ref "U11") (pin "6") (pinfunction "VDD_6") (pintype "bidirectional"))
    )
    (net (code "59") (name "/VIN") (class "Default")
      (node (ref "C42") (pin "2") (pinfunction "2_2") (pintype "passive"))
      (node (ref "C6") (pin "2") (pinfunction "2_2") (pintype "passive"))
      (node (ref "D1") (pin "2") (pinfunction "-_2") (pintype "passive"))
      (node (ref "D2") (pin "C") (pinfunction "C_C") (pintype "passive"))
      (node (ref "Q3") (pin "2") (pinfunction "S_2") (pintype "bidirectional"))
      (node (ref "Q30") (pin "2") (pinfunction "S_2") (pintype "bidirectional"))
      (node (ref "R172") (pin "1") (pinfunction "1_1") (pintype "passive"))
      (node (ref "R18/NC") (pin "1") (pinfunction "1_1") (pintype "passive"))
      (node (ref "U1") (pin "1") (pinfunction "EN_1") (pintype "bidirectional"))
      (node (ref "U1") (pin "4") (pinfunction "VIN_4") (pintype "bidirectional"))
    )
    (net (code "60") (name "/VIN2") (class "Default")
      (node (ref "C18") (pin "2") (pinfunction "2_2") (pintype "passive"))
      (node (ref "C43") (pin "2") (pinfunction "2_2") (pintype "passive"))
      (node (ref "L5") (pin "1") (pinfunction "1_1") (pintype "bidirectional"))
      (node (ref "Q30") (pin "3") (pinfunction "D_3") (pintype "bidirectional"))
      (node (ref "R15") (pin "2") (pinfunction "2_2") (pintype "passive"))
      (node (ref "U4") (pin "6") (pinfunction "6-VIN_6") (pintype "bidirectional"))
    )
    (net (code "61") (name "GND") (class "Default")
      (node (ref "C1") (pin "1") (pinfunction "1_1") (pintype "bidirectional"))
      (node (ref "C10") (pin "1") (pinfunction "1_1") (pintype "passive"))
      (node (ref "C11") (pin "2") (pinfunction "2_2") (pintype "passive"))
      (node (ref "C12") (pin "1") (pinfunction "1_1") (pintype "passive"))
      (node (ref "C13") (pin "2") (pinfunction "2_2") (pintype "passive"))
      (node (ref "C14") (pin "2") (pinfunction "2_2") (pintype "passive"))
      (node (ref "C15") (pin "1") (pinfunction "1_1") (pintype "passive"))
      (node (ref "C16") (pin "2") (pinfunction "2_2") (pintype "passive"))
      (node (ref "C17") (pin "1") (pinfunction "1_1") (pintype "passive"))
      (node (ref "C18") (pin "1") (pinfunction "1_1") (pintype "passive"))
      (node (ref "C19") (pin "1") (pinfunction "1_1") (pintype "passive"))
      (node (ref "C2") (pin "2") (pinfunction "2_2") (pintype "passive"))
      (node (ref "C20") (pin "2") (pinfunction "2_2") (pintype "passive"))
      (node (ref "C21") (pin "1") (pinfunction "1_1") (pintype "passive"))
      (node (ref "C22") (pin "1") (pinfunction "1_1") (pintype "passive"))
      (node (ref "C23") (pin "1") (pinfunction "1_1") (pintype "passive"))
      (node (ref "C24") (pin "2") (pinfunction "2_2") (pintype "passive"))
      (node (ref "C25") (pin "2") (pinfunction "2_2") (pintype "passive"))
      (node (ref "C26") (pin "2") (pinfunction "2_2") (pintype "passive"))
      (node (ref "C27") (pin "1") (pinfunction "1_1") (pintype "passive"))
      (node (ref "C28") (pin "1") (pinfunction "1_1") (pintype "passive"))
      (node (ref "C29") (pin "1") (pinfunction "1_1") (pintype "passive"))
      (node (ref "C3") (pin "2") (pinfunction "2_2") (pintype "passive"))
      (node (ref "C30") (pin "1") (pinfunction "1_1") (pintype "passive"))
      (node (ref "C31") (pin "1") (pinfunction "1_1") (pintype "passive"))
      (node (ref "C32") (pin "1") (pinfunction "1_1") (pintype "passive"))
      (node (ref "C33") (pin "2") (pinfunction "2_2") (pintype "passive"))
      (node (ref "C34") (pin "1") (pinfunction "1_1") (pintype "bidirectional"))
      (node (ref "C35") (pin "1") (pinfunction "1_1") (pintype "passive"))
      (node (ref "C36") (pin "1") (pinfunction "1_1") (pintype "passive"))
      (node (ref "C39") (pin "2") (pinfunction "2_2") (pintype "passive"))
      (node (ref "C4") (pin "1") (pinfunction "1_1") (pintype "passive"))
      (node (ref "C42") (pin "1") (pinfunction "1_1") (pintype "passive"))
      (node (ref "C43") (pin "1") (pinfunction "1_1") (pintype "passive"))
      (node (ref "C5") (pin "1") (pinfunction "1_1") (pintype "bidirectional"))
      (node (ref "C54") (pin "1") (pinfunction "1_1") (pintype "passive"))
      (node (ref "C6") (pin "1") (pinfunction "1_1") (pintype "passive"))
      (node (ref "C7") (pin "1") (pinfunction "1_1") (pintype "passive"))
      (node (ref "C8") (pin "1") (pinfunction "1_1") (pintype "passive"))
      (node (ref "C9") (pin "1") (pinfunction "1_1") (pintype "passive"))
      (node (ref "J1") (pin "P$2") (pinfunction "P$2_P$2") (pintype "bidirectional"))
      (node (ref "J1") (pin "P$3") (pinfunction "P$3_P$3") (pintype "bidirectional"))
      (node (ref "J1") (pin "P$4") (pinfunction "P$4_P$4") (pintype "bidirectional"))
      (node (ref "J10") (pin "4") (pinfunction "4_4") (pintype "bidirectional"))
      (node (ref "J10") (pin "SS1") (pinfunction "SS1_SS1") (pintype "bidirectional"))
      (node (ref "J10") (pin "SS2") (pinfunction "SS2_SS2") (pintype "bidirectional"))
      (node (ref "J3") (pin "A1") (pinfunction "GND_A1") (pintype "bidirectional"))
      (node (ref "J3") (pin "A12") (pinfunction "GND_A12") (pintype "bidirectional"))
      (node (ref "J3") (pin "B1") (pinfunction "GND_B1") (pintype "bidirectional"))
      (node (ref "J3") (pin "B12") (pinfunction "GND_B12") (pintype "bidirectional"))
      (node (ref "J3") (pin "P$6") (pinfunction "P$17_P$6") (pintype "bidirectional"))
      (node (ref "J3") (pin "P$7") (pinfunction "P$18_P$7") (pintype "bidirectional"))
      (node (ref "J3") (pin "P$8") (pinfunction "P$19_P$8") (pintype "bidirectional"))
      (node (ref "J3") (pin "P$9") (pinfunction "P$20_P$9") (pintype "bidirectional"))
      (node (ref "J4") (pin "3") (pinfunction "P$3_3") (pintype "bidirectional"))
      (node (ref "J4") (pin "4") (pinfunction "P$4_4") (pintype "bidirectional"))
      (node (ref "J5") (pin "P$3") (pinfunction "P$3_P$3") (pintype "bidirectional"))
      (node (ref "J5") (pin "P$4") (pinfunction "P$4_P$4") (pintype "bidirectional"))
      (node (ref "J7") (pin "4") (pinfunction "4_4") (pintype "bidirectional"))
      (node (ref "J7") (pin "SS1") (pinfunction "SS1_SS1") (pintype "bidirectional"))
      (node (ref "J7") (pin "SS2") (pinfunction "SS2_SS2") (pintype "bidirectional"))
      (node (ref "JP1") (pin "P$12") (pinfunction "GND4_P$12") (pintype "bidirectional"))
      (node (ref "JP1") (pin "P$18") (pinfunction "B2_P$18") (pintype "bidirectional"))
      (node (ref "JP1") (pin "P$19") (pinfunction "B1_P$19") (pintype "bidirectional"))
      (node (ref "JP1") (pin "P$20") (pinfunction "B0_P$20") (pintype "bidirectional"))
      (node (ref "JP1") (pin "P$27") (pinfunction "G1_P$27") (pintype "bidirectional"))
      (node (ref "JP1") (pin "P$28") (pinfunction "G0_P$28") (pintype "bidirectional"))
      (node (ref "JP1") (pin "P$34") (pinfunction "R2_P$34") (pintype "bidirectional"))
      (node (ref "JP1") (pin "P$35") (pinfunction "R1_P$35") (pintype "bidirectional"))
      (node (ref "JP1") (pin "P$36") (pinfunction "R0_P$36") (pintype "bidirectional"))
      (node (ref "JP1") (pin "P$38") (pinfunction "GND3_P$38") (pintype "bidirectional"))
      (node (ref "JP1") (pin "P$41") (pinfunction "GND5_P$41") (pintype "bidirectional"))
      (node (ref "JP1") (pin "P$42") (pinfunction "GND6_P$42") (pintype "bidirectional"))
      (node (ref "JP1") (pin "P$5") (pinfunction "GND2_P$5") (pintype "bidirectional"))
      (node (ref "K1") (pin "1") (pinfunction "1_1") (pintype "passive"))
      (node (ref "K4") (pin "1") (pinfunction "1_1") (pintype "passive"))
      (node (ref "LED1") (pin "-") (pinfunction "-_-") (pintype "passive"))
      (node (ref "Q5") (pin "2") (pinfunction "E_2") (pintype "passive"))
      (node (ref "R1") (pin "1") (pinfunction "1_1") (pintype "passive"))
      (node (ref "R13") (pin "1") (pinfunction "1_1") (pintype "passive"))
      (node (ref "R14") (pin "2") (pinfunction "2_2") (pintype "passive"))
      (node (ref "R21") (pin "2") (pinfunction "2_2") (pintype "passive"))
      (node (ref "R28") (pin "2") (pinfunction "2_2") (pintype "passive"))
      (node (ref "R29") (pin "2") (pinfunction "2_2") (pintype "passive"))
      (node (ref "R31") (pin "1") (pinfunction "1_1") (pintype "passive"))
      (node (ref "R32") (pin "2") (pinfunction "2_2") (pintype "passive"))
      (node (ref "R5") (pin "1") (pinfunction "1_1") (pintype "passive"))
      (node (ref "R58") (pin "1") (pinfunction "1_1") (pintype "passive"))
      (node (ref "SD1") (pin "6") (pinfunction "VSS_6") (pintype "bidirectional"))
      (node (ref "SD1") (pin "G1") (pinfunction "G1_G1") (pintype "bidirectional"))
      (node (ref "SD1") (pin "G2") (pinfunction "G2_G2") (pintype "bidirectional"))
      (node (ref "SD1") (pin "G3") (pinfunction "G3_G3") (pintype "bidirectional"))
      (node (ref "SD1") (pin "G4") (pinfunction "G4_G4") (pintype "bidirectional"))
      (node (ref "U1") (pin "2") (pinfunction "GND_2") (pintype "bidirectional"))
      (node (ref "U11") (pin "7") (pinfunction "GND_7") (pintype "bidirectional"))
      (node (ref "U2") (pin "1") (pinfunction "GND1_1") (pintype "bidirectional"))
      (node (ref "U2") (pin "40") (pinfunction "GND2_40") (pintype "bidirectional"))
      (node (ref "U2") (pin "41") (pinfunction "GND3_41") (pintype "bidirectional"))
      (node (ref "U2") (pin "42") (pinfunction "GND4_42") (pintype "bidirectional"))
      (node (ref "U2") (pin "43") (pinfunction "GND5_43") (pintype "bidirectional"))
      (node (ref "U2") (pin "44") (pinfunction "GND6_44") (pintype "bidirectional"))
      (node (ref "U2") (pin "45") (pinfunction "GND7_45") (pintype "bidirectional"))
      (node (ref "U2") (pin "46") (pinfunction "GND8_46") (pintype "bidirectional"))
      (node (ref "U2") (pin "47") (pinfunction "GND9_47") (pintype "bidirectional"))
      (node (ref "U2") (pin "48") (pinfunction "GND10_48") (pintype "bidirectional"))
      (node (ref "U2") (pin "49") (pinfunction "GND11_49") (pintype "bidirectional"))
      (node (ref "U26") (pin "2") (pinfunction "GND_2") (pintype "bidirectional"))
      (node (ref "U4") (pin "2") (pinfunction "2-GND_2") (pintype "bidirectional"))
      (node (ref "U41") (pin "6") (pinfunction "GND_6") (pintype "bidirectional"))
      (node (ref "U6") (pin "1") (pinfunction "GND_1") (pintype "bidirectional"))
    )
    (net (code "62") (name "Net-(C14-Pad1)") (class "Default")
      (node (ref "C14") (pin "1") (pinfunction "1_1") (pintype "passive"))
      (node (ref "C37") (pin "1") (pinfunction "1_1") (pintype "passive"))
      (node (ref "J5") (pin "P$2") (pinfunction "P$2_P$2") (pintype "bidirectional"))
    )
    (net (code "63") (name "Net-(C16-Pad1)") (class "Default")
      (node (ref "C16") (pin "1") (pinfunction "1_1") (pintype "passive"))
      (node (ref "C38") (pin "1") (pinfunction "1_1") (pintype "passive"))
      (node (ref "J5") (pin "P$1") (pinfunction "P$1_P$1") (pintype "bidirectional"))
    )
    (net (code "64") (name "Net-(D6-+)") (class "Default")
      (node (ref "D6") (pin "1") (pinfunction "+_1") (pintype "passive"))
      (node (ref "L5") (pin "2") (pinfunction "2_2") (pintype "bidirectional"))
      (node (ref "U4") (pin "1") (pinfunction "1-SW_1") (pintype "bidirectional"))
    )
    (net (code "65") (name "Net-(J3-CC1)") (class "Default")
      (node (ref "J3") (pin "A5") (pinfunction "CC1_A5") (pintype "bidirectional"))
      (node (ref "R13") (pin "2") (pinfunction "2_2") (pintype "passive"))
    )
    (net (code "66") (name "Net-(J3-CC2)") (class "Default")
      (node (ref "J3") (pin "B5") (pinfunction "CC2_B5") (pintype "bidirectional"))
      (node (ref "R14") (pin "1") (pinfunction "1_1") (pintype "passive"))
    )
    (net (code "67") (name "Net-(JP1-DISP)") (class "Default")
      (node (ref "JP1") (pin "P$10") (pinfunction "DISP_P$10") (pintype "bidirectional"))
      (node (ref "R25") (pin "2") (pinfunction "2_2") (pintype "passive"))
    )
    (net (code "68") (name "Net-(L4-P$1)") (class "Default")
      (node (ref "L4") (pin "1") (pinfunction "P$1_1") (pintype "bidirectional"))
      (node (ref "U1") (pin "3") (pinfunction "SW_3") (pintype "bidirectional"))
    )
    (net (code "69") (name "Net-(LED1-Pad+)") (class "Default")
      (node (ref "LED1") (pin "+") (pinfunction "+_+") (pintype "passive"))
      (node (ref "R3") (pin "1") (pinfunction "1_1") (pintype "passive"))
    )
    (net (code "70") (name "Net-(Q3-G)") (class "Default")
      (node (ref "Q3") (pin "1") (pinfunction "G_1") (pintype "bidirectional"))
      (node (ref "R27") (pin "1") (pinfunction "1_1") (pintype "passive"))
      (node (ref "R5") (pin "2") (pinfunction "2_2") (pintype "passive"))
    )
    (net (code "71") (name "Net-(Q5-B)") (class "Default")
      (node (ref "Q5") (pin "1") (pinfunction "B_1") (pintype "passive"))
      (node (ref "R11") (pin "1") (pinfunction "1_1") (pintype "passive"))
      (node (ref "R58") (pin "2") (pinfunction "2_2") (pintype "passive"))
    )
    (net (code "72") (name "Net-(Q9-B)") (class "Default")
      (node (ref "Q9") (pin "1") (pinfunction "B_1") (pintype "passive"))
      (node (ref "R75") (pin "1") (pinfunction "1_1") (pintype "passive"))
    )
    (net (code "73") (name "Net-(Q10-B)") (class "Default")
      (node (ref "Q10") (pin "1") (pinfunction "B_1") (pintype "passive"))
      (node (ref "R74") (pin "1") (pinfunction "1_1") (pintype "passive"))
    )
    (net (code "74") (name "Net-(Q30-G)") (class "Default")
      (node (ref "Q30") (pin "1") (pinfunction "G_1") (pintype "bidirectional"))
      (node (ref "Q5") (pin "3") (pinfunction "C_3") (pintype "passive"))
      (node (ref "R172") (pin "2") (pinfunction "2_2") (pintype "passive"))
    )
    (net (code "75") (name "Net-(SD1-DATA1)") (class "Default")
      (node (ref "R17") (pin "2") (pinfunction "2_2") (pintype "passive"))
      (node (ref "SD1") (pin "8") (pinfunction "DATA1_8") (pintype "bidirectional"))
    )
    (net (code "76") (name "Net-(SD1-DATA2)") (class "Default")
      (node (ref "R16") (pin "2") (pinfunction "2_2") (pintype "passive"))
      (node (ref "SD1") (pin "1") (pinfunction "DATA2_1") (pintype "bidirectional"))
    )
    (net (code "77") (name "Net-(U1-FB)") (class "Default")
      (node (ref "R20") (pin "2") (pinfunction "2_2") (pintype "passive"))
      (node (ref "R21") (pin "1") (pinfunction "1_1") (pintype "passive"))
      (node (ref "U1") (pin "5") (pinfunction "FB_5") (pintype "bidirectional"))
    )
    (net (code "78") (name "Net-(U6-RXD)") (class "Default")
      (node (ref "R71") (pin "2") (pinfunction "2_2") (pintype "passive"))
      (node (ref "U6") (pin "3") (pinfunction "RXD_3") (pintype "bidirectional"))
    )
    (net (code "79") (name "Net-(U6-TXD)") (class "Default")
      (node (ref "R72") (pin "2") (pinfunction "2_2") (pintype "passive"))
      (node (ref "U6") (pin "2") (pinfunction "TXD_2") (pintype "bidirectional"))
    )
    (net (code "80") (name "Net-(U11-VON)") (class "Default")
      (node (ref "C38") (pin "2") (pinfunction "2_2") (pintype "passive"))
      (node (ref "U11") (pin "5") (pinfunction "VON_5") (pintype "bidirectional"))
    )
    (net (code "81") (name "Net-(U11-VOP)") (class "Default")
      (node (ref "C37") (pin "2") (pinfunction "2_2") (pintype "passive"))
      (node (ref "U11") (pin "8") (pinfunction "VOP_8") (pintype "bidirectional"))
    )
    (net (code "82") (name "Net-(U26-PROG)") (class "Default")
      (node (ref "R28") (pin "1") (pinfunction "1_1") (pintype "passive"))
      (node (ref "U26") (pin "5") (pinfunction "PROG_5") (pintype "bidirectional"))
    )
    (net (code "83") (name "Net-(U41-CS)") (class "Default")
      (node (ref "R1") (pin "2") (pinfunction "2_2") (pintype "passive"))
      (node (ref "R2") (pin "2") (pinfunction "2_2") (pintype "passive"))
      (node (ref "U41") (pin "15") (pinfunction "CS_15") (pintype "bidirectional"))
    )
    (net (code "84") (name "Net-(U41-VBAT)") (class "Default")
      (node (ref "R41") (pin "2") (pinfunction "2_2") (pintype "passive"))
      (node (ref "U41") (pin "7") (pinfunction "VBAT_7") (pintype "bidirectional"))
    )
    (net (code "85") (name "unconnected-(J3-SBU1-PadA8)") (class "Default")
      (node (ref "J3") (pin "A8") (pinfunction "SBU1_A8") (pintype "bidirectional"))
    )
    (net (code "86") (name "unconnected-(J3-SBU2-PadB8)") (class "Default")
      (node (ref "J3") (pin "B8") (pinfunction "SBU2_B8") (pintype "bidirectional"))
    )
    (net (code "87") (name "unconnected-(JP1-NC-PadP$6)") (class "Default")
      (node (ref "JP1") (pin "P$6") (pinfunction "NC_P$6") (pintype "bidirectional"))
    )
    (net (code "88") (name "unconnected-(SD1-CDN-Pad9)") (class "Default")
      (node (ref "SD1") (pin "9") (pinfunction "CDN_9") (pintype "bidirectional"))
    )
    (net (code "89") (name "unconnected-(U6-CTS#-Pad9)") (class "Default")
      (node (ref "U6") (pin "9") (pinfunction "CTS#_9") (pintype "bidirectional"))
    )
    (net (code "90") (name "unconnected-(U6-DCD#-Pad12)") (class "Default")
      (node (ref "U6") (pin "12") (pinfunction "DCD#_12") (pintype "bidirectional"))
    )
    (net (code "91") (name "unconnected-(U6-DSR#-Pad10)") (class "Default")
      (node (ref "U6") (pin "10") (pinfunction "DSR#_10") (pintype "bidirectional"))
    )
    (net (code "92") (name "unconnected-(U6-RI#-Pad11)") (class "Default")
      (node (ref "U6") (pin "11") (pinfunction "RI#_11") (pintype "bidirectional"))
    )
    (net (code "93") (name "unconnected-(U6-RS232-Pad15)") (class "Default")
      (node (ref "U6") (pin "15") (pinfunction "RS232_15") (pintype "bidirectional"))
    )
    (net (code "94") (name "unconnected-(U6-XI-Pad7)") (class "Default")
      (node (ref "U6") (pin "7") (pinfunction "XI_7") (pintype "bidirectional"))
    )
    (net (code "95") (name "unconnected-(U6-XO-Pad8)") (class "Default")
      (node (ref "U6") (pin "8") (pinfunction "XO_8") (pintype "bidirectional"))
    )
    (net (code "96") (name "unconnected-(U11-PE-Pad9)") (class "Default")
      (node (ref "U11") (pin "9") (pinfunction "PE_9") (pintype "bidirectional"))
    )
    (net (code "97") (name "unconnected-(U26-GHRG-Pad1)") (class "Default")
      (node (ref "U26") (pin "1") (pinfunction "GHRG_1") (pintype "bidirectional"))
    )
    (net (code "98") (name "unconnected-(U41-BUESY-Pad13)") (class "Default")
      (node (ref "U41") (pin "13") (pinfunction "BUESY_13") (pintype "bidirectional"))
    )
    (net (code "99") (name "unconnected-(U41-IN-Pad8)") (class "Default")
      (node (ref "U41") (pin "8") (pinfunction "IN_8") (pintype "bidirectional"))
    )
  )
)
